# 0001_Page_1.net
KiCad netlist of a schematic drawn in Altium Designer
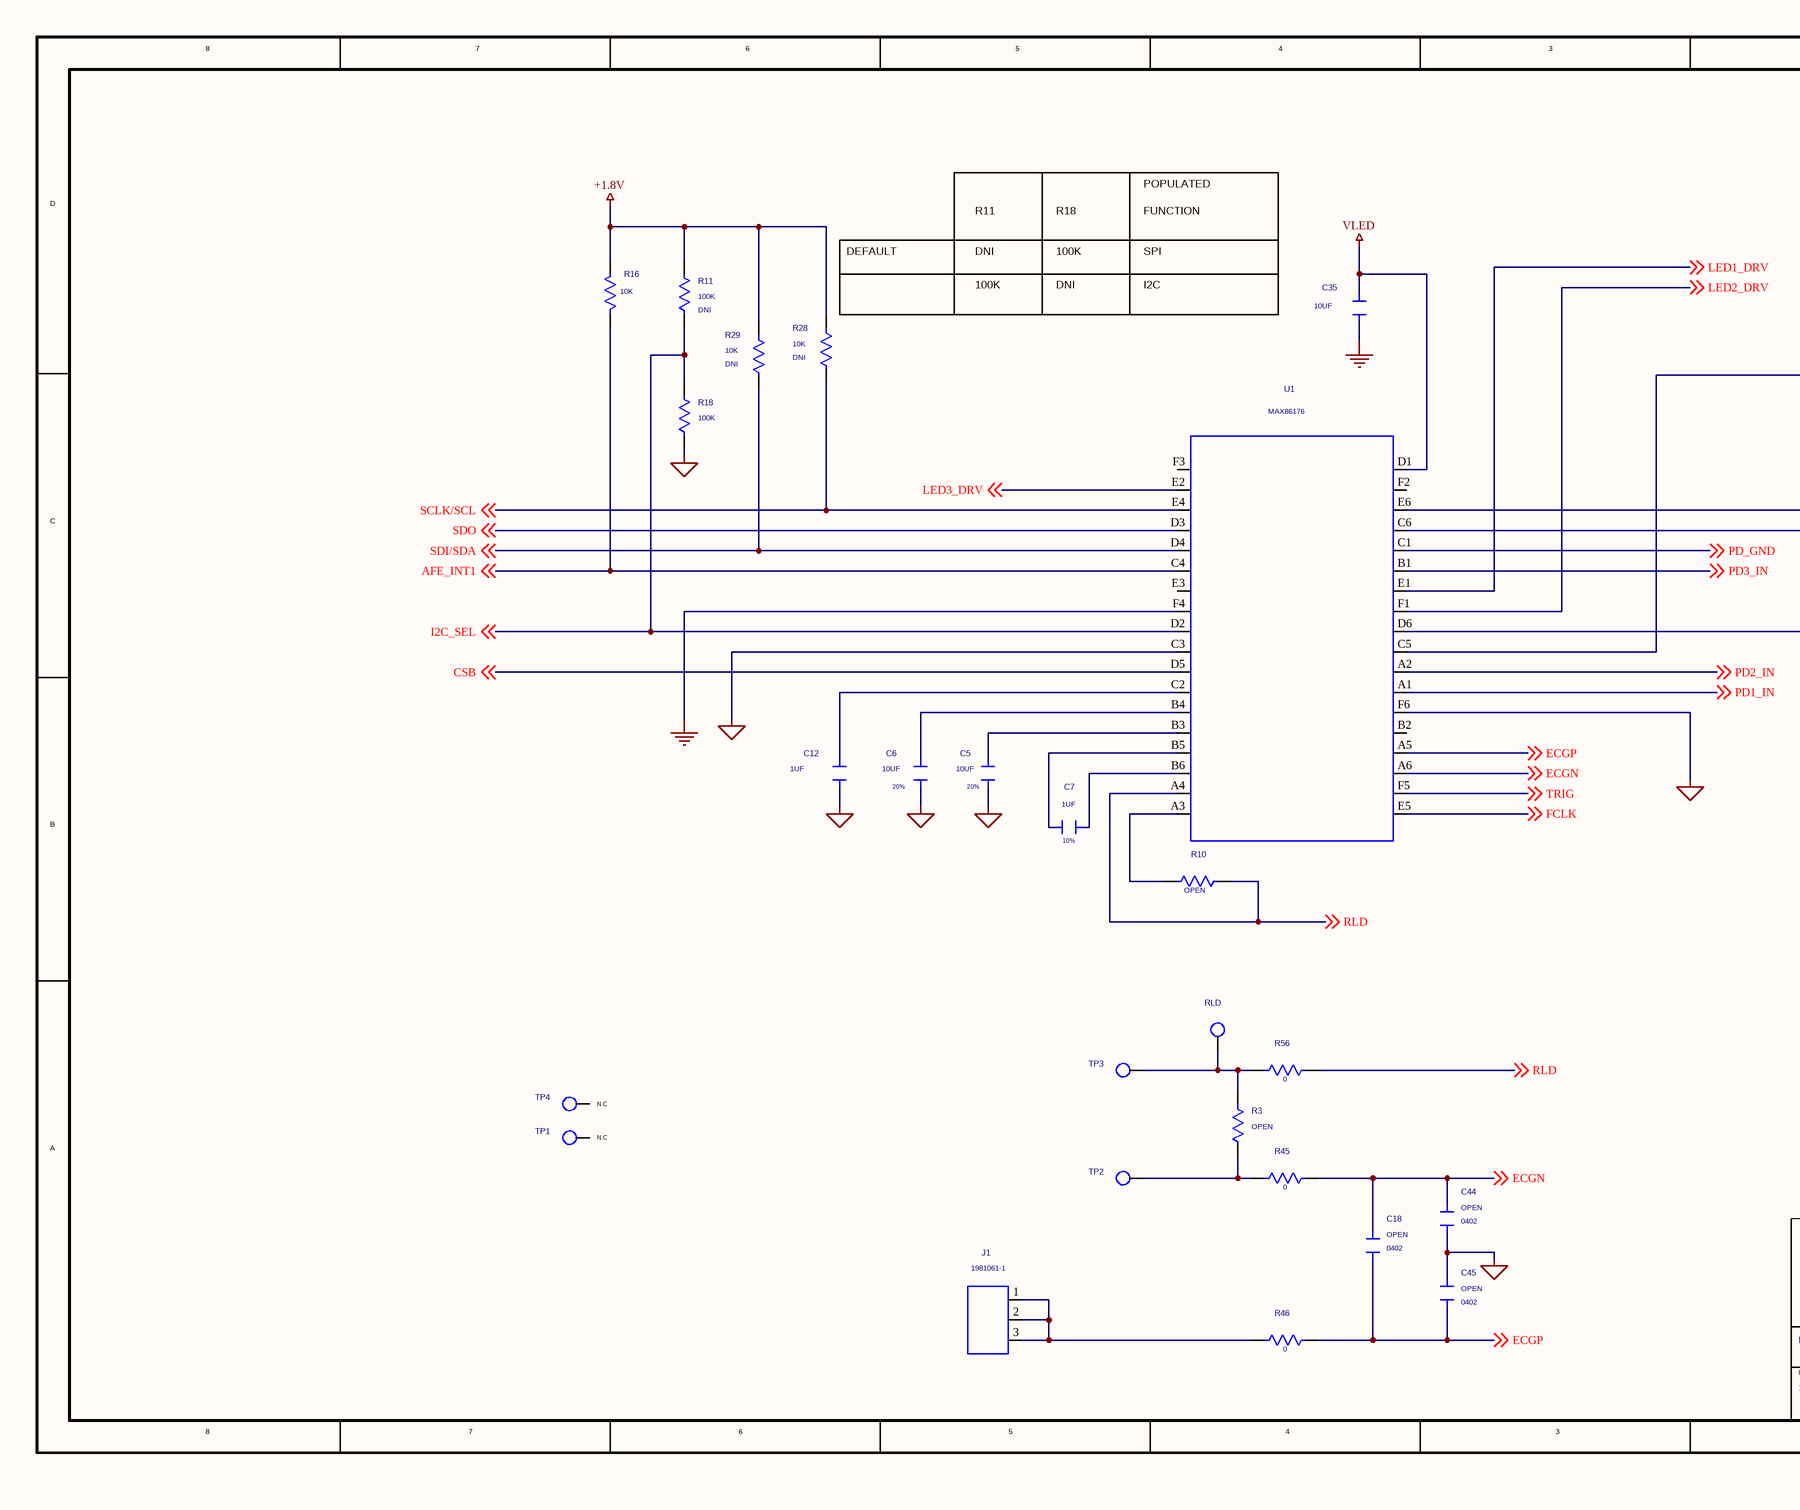
[diagram p0: 0001_Page 1.SchDoc, left]
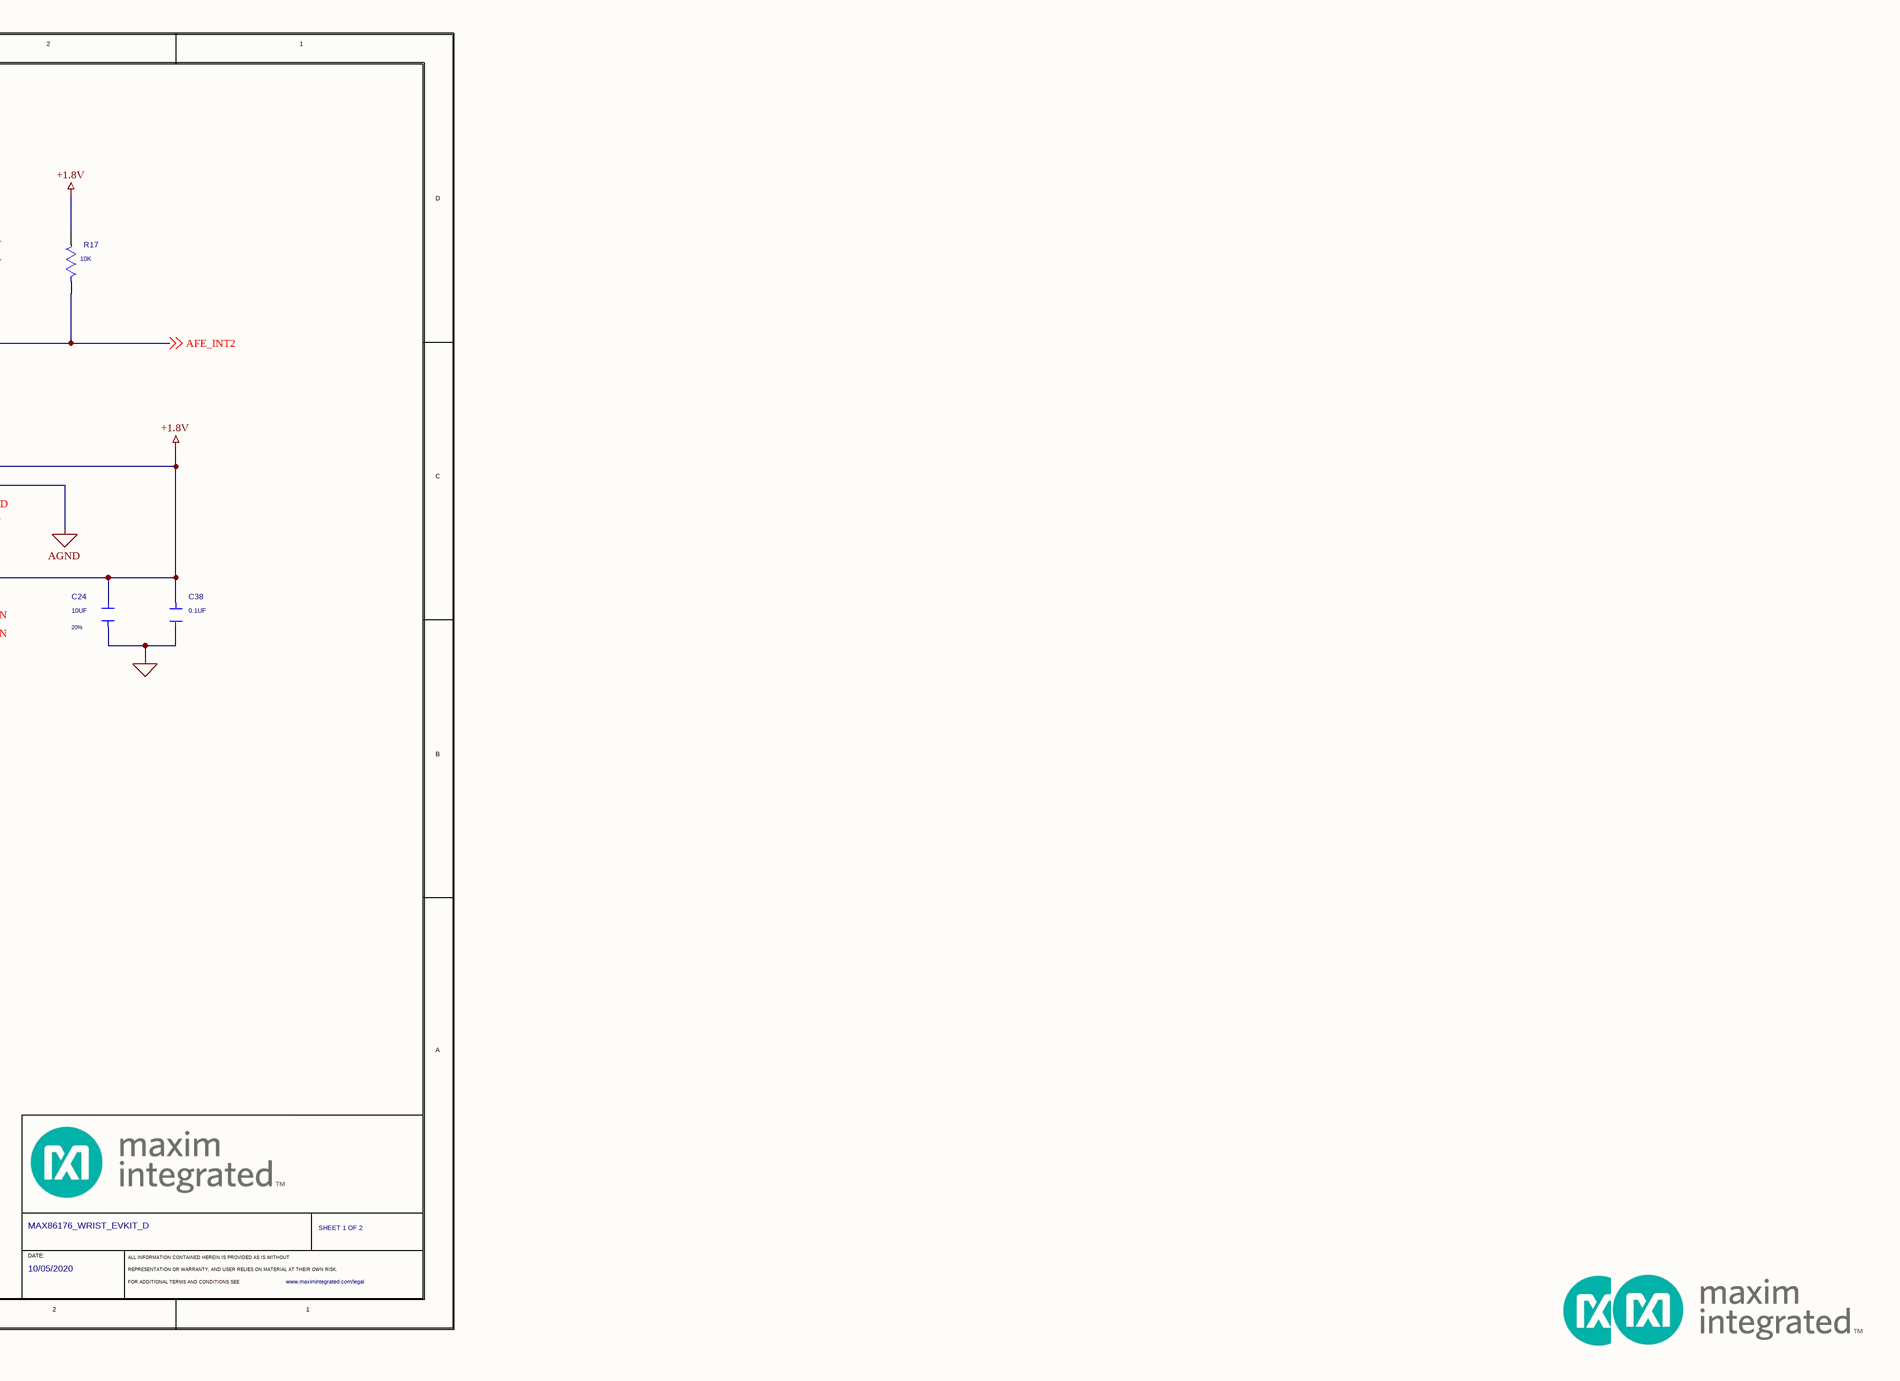
[diagram p1: 0001_Page 1.SchDoc, right]

(export (version "E")
  (design (tool "Eeschema 10.0.6"))
  (components
    (comp (ref "C5")
      (value "10UF")
      (footprint "0402")
      (description "CAP; SMT (0402); 10UF; 20%; 10V; X5R; CERAMIC")
      (fields
        (field (name "MFG_PART_NUMBER") "GRM155R61A106ME44;GRM155R61A106ME11;0402ZD106MAT2A;CL05A106MP5NUNC")
        (field (name "TOLERANCE") "20%")
        (field (name "MANUFACTURER") "MURATA;MURATA;AVX;SAMSUNG")
      )
      (libsource (lib "*") (part "CAP_NP#1"))
    )
    (comp (ref "C6")
      (value "10UF")
      (footprint "0402")
      (description "CAP; SMT (0402); 10UF; 20%; 10V; X5R; CERAMIC")
      (fields
        (field (name "MFG_PART_NUMBER") "GRM155R61A106ME44;GRM155R61A106ME11;0402ZD106MAT2A;CL05A106MP5NUNC")
        (field (name "TOLERANCE") "20%")
        (field (name "MANUFACTURER") "MURATA;MURATA;AVX;SAMSUNG")
      )
      (libsource (lib "*") (part "CAP_NP#1"))
    )
    (comp (ref "C7")
      (value "1UF")
      (footprint "0603")
      (description "CAP; SMT (0603); 1UF; 10%; 25V; X7R; CERAMIC")
      (fields
        (field (name "TOLERANCE") "10%")
        (field (name "MANUFACTURER") "MURATA;TAIYO YUDEN;AVX;TAIYO YUDEN")
      )
      (libsource (lib "*") (part "CAP_NP#1"))
    )
    (comp (ref "C12")
      (value "1UF")
      (footprint "0402")
      (description "CAP; SMT (0402); 1UF; 10%; 16V; X5R; CERAMIC")
      (fields (field (name "MFG_PART_NUMBER") "CL05A105KO5NNN") (field (name "TOLERANCE") "10%"))
      (libsource (lib "*") (part "CAP_NP"))
    )
    (comp (ref "C18")
      (value "OPEN")
      (footprint "0402")
      (description "PACKAGE OUTLINE 0402 NON-POLAR CAPACITOR - EVKIT")
      (fields (field (name "PCB FOOTPRINT_CDS") "0402"))
      (libsource (lib "*") (part "EVK_GENERIC_CAPACITORS"))
    )
    (comp (ref "C24")
      (value "10UF")
      (footprint "0603")
      (description "CAP; SMT (0603); 10UF; 20%; 25V; X5R; CERAMIC CHIP")
      (fields
        (field (name "MFG_PART_NUMBER") "GRM188R61E106MA73")
        (field (name "TOLERANCE") "20%")
        (field (name "MANUFACTURER") "MURATA")
      )
      (libsource (lib "*") (part "EK_CAP_NP#1"))
    )
    (comp (ref "C35")
      (value "10UF")
      (footprint "0603")
      (description "CAP; SMT (0603); 10UF; 20%; 25V; X5R; CERAMIC CHIP")
      (fields (field (name "MFG_PART_NUMBER") "GRM188R61E106MA73") (field (name "TOLERANCE") "20%"))
      (libsource (lib "*") (part "EK_CAP_NP"))
    )
    (comp (ref "C38")
      (value "0.1UF")
      (footprint "0603")
      (description "CAP; SMT (0603); 0.1UF; 10%; 100V; X7R; CERAMIC")
      (fields
        (field (name "MFG_PART_NUMBER") "GRM188R72A104KA35; CC0603KRX7R0BB104")
        (field (name "TOLERANCE") "10%")
      )
      (libsource (lib "*") (part "CAP_NP"))
    )
    (comp (ref "C44")
      (value "OPEN")
      (footprint "0402")
      (description "PACKAGE OUTLINE 0402 NON-POLAR CAPACITOR - EVKIT")
      (fields (field (name "PCB FOOTPRINT_CDS") "0402"))
      (libsource (lib "*") (part "EVK_GENERIC_CAPACITORS"))
    )
    (comp (ref "C45")
      (value "OPEN")
      (footprint "0402")
      (description "PACKAGE OUTLINE 0402 NON-POLAR CAPACITOR - EVKIT")
      (fields (field (name "PCB FOOTPRINT_CDS") "0402"))
      (libsource (lib "*") (part "EVK_GENERIC_CAPACITORS"))
    )
    (comp (ref "J1")
      (value "1981061-1")
      (footprint "TECO_1981061-1")
      (description "CONNECTOR; MALE; SMD; LEAF TYPE BATTERY CONNECTOR; WITHOUT BOSS; 3 PINS")
      (fields (field (name "MANUFACTURER") "TYCO"))
      (libsource (lib "*") (part "1981061-1"))
    )
    (comp (ref "R3")
      (value "OPEN")
      (footprint "RESC0603X33M")
      (description "PACKAGE OUTLINE 0201 RESISTOR - EVKIT")
      (libsource (lib "*") (part "EVK_GENERIC_RESISTORS#1"))
    )
    (comp (ref "R10")
      (value "OPEN")
      (footprint "0402")
      (description "PACKAGE OUTLINE 0402 RESISTOR - EVKIT")
      (libsource (lib "*") (part "EVK_GENERIC_RESISTORS"))
    )
    (comp (ref "R11")
      (value "100K")
      (footprint "0402")
      (description "RES; SMT (0402); 100K; 1%; +/-100PPM/DEGC; 0.1000W")
      (fields
        (field (name "MFG_PART_NUMBER") "ERJ-2RKF1003")
        (field (name "TOLERANCE") "1%")
        (field (name "VARIANT") "DNI")
      )
      (libsource (lib "*") (part "RES_SMD#1"))
    )
    (comp (ref "R16")
      (value "10K")
      (footprint "0402")
      (description "RES; SMT (0402); 10K; 1%; +/-100PPM/DEGC; 0.1000W")
      (fields (field (name "MFG_PART_NUMBER") "ERJ-2RKF1002") (field (name "TOLERANCE") "1%"))
      (libsource (lib "*") (part "RES_SMD"))
    )
    (comp (ref "R17")
      (value "10K")
      (footprint "0402")
      (description "RES; SMT (0402); 10K; 1%; +/-100PPM/DEGC; 0.1000W")
      (fields (field (name "MFG_PART_NUMBER") "ERJ-2RKF1002") (field (name "TOLERANCE") "1%"))
      (libsource (lib "*") (part "RES_SMD"))
    )
    (comp (ref "R18")
      (value "100K")
      (footprint "0402")
      (description "RES; SMT (0402); 100K; 1%; +/-100PPM/DEGC; 0.1000W")
      (fields (field (name "MFG_PART_NUMBER") "ERJ-2RKF1003") (field (name "TOLERANCE") "1%"))
      (libsource (lib "*") (part "RES_SMD#1"))
    )
    (comp (ref "R28")
      (value "10K")
      (footprint "0402")
      (description "RES; SMT (0402); 10K; 1%; +/-100PPM/DEGC; 0.1000W")
      (fields
        (field (name "MFG_PART_NUMBER") "ERJ-2RKF1002")
        (field (name "TOLERANCE") "1%")
        (field (name "VARIANT") "DNI")
      )
      (libsource (lib "*") (part "RES_SMD"))
    )
    (comp (ref "R29")
      (value "10K")
      (footprint "0402")
      (description "RES; SMT (0402); 10K; 1%; +/-100PPM/DEGC; 0.1000W")
      (fields
        (field (name "MFG_PART_NUMBER") "ERJ-2RKF1002")
        (field (name "TOLERANCE") "1%")
        (field (name "VARIANT") "DNI")
      )
      (libsource (lib "*") (part "RES_SMD"))
    )
    (comp (ref "R45")
      (value "0")
      (footprint "0402")
      (description "RES; SMT (0402); 0; JUMPER; JUMPER; 0.1000W")
      (fields (field (name "MFG_PART_NUMBER") "ERJ-2GE0R00") (field (name "TOLERANCE") "0%"))
      (libsource (lib "*") (part "RES_SMD#1"))
    )
    (comp (ref "R46")
      (value "0")
      (footprint "0402")
      (description "RES; SMT (0402); 0; JUMPER; JUMPER; 0.1000W")
      (fields (field (name "MFG_PART_NUMBER") "ERJ-2GE0R00") (field (name "TOLERANCE") "0%"))
      (libsource (lib "*") (part "RES_SMD#1"))
    )
    (comp (ref "R56")
      (value "0")
      (footprint "0402")
      (description "RES; SMT (0402); 0; JUMPER; JUMPER; 0.1000W")
      (fields (field (name "MFG_PART_NUMBER") "ERJ-2GE0R00") (field (name "TOLERANCE") "0%"))
      (libsource (lib "*") (part "RES_SMD#1"))
    )
    (comp (ref "RLD")
      (value "N/A")
      (footprint "TP_C25H12")
      (description "TESTPOINT WITH 12 MILS HOLE DIA, and 25 MILS PAD DIA; NOT FOR COLD TEST")
      (libsource (lib "*") (part "TP"))
    )
    (comp (ref "TP1")
      (value "N/A")
      (footprint "TP_S_SQUARE_3-50")
      (description "TESTPOINT WITH 3.50MM SQUARE PAD DIAMETER")
      (libsource (lib "*") (part "TP"))
    )
    (comp (ref "TP2")
      (value "N/A")
      (footprint "TP_S_SQUARE_3-50")
      (description "TESTPOINT WITH 3.50MM SQUARE PAD DIAMETER")
      (libsource (lib "*") (part "TP"))
    )
    (comp (ref "TP3")
      (value "N/A")
      (footprint "TP_S_SQUARE_3-50")
      (description "TESTPOINT WITH 3.50MM SQUARE PAD DIAMETER")
      (libsource (lib "*") (part "TP"))
    )
    (comp (ref "TP4")
      (value "N/A")
      (footprint "TP_S_SQUARE_3-50")
      (description "TESTPOINT WITH 3.50MM SQUARE PAD DIAMETER")
      (libsource (lib "*") (part "TP"))
    )
    (comp (ref "U1")
      (value "MAX86176")
      (footprint "MAXIM_21-100413")
      (fields (field (name "MANUFACTURER") "MAXIM"))
      (libsource (lib "*") (part "EK_MAX86176"))
    )
  )
  (nets
    (net (code "1") (name "+1.8V") (class "Default")
      (node (ref "C24") (pin "2") (pinfunction "2_2") (pintype "bidirectional"))
      (node (ref "C38") (pin "2") (pinfunction "2_2") (pintype "bidirectional"))
      (node (ref "R11") (pin "2") (pinfunction "2_2") (pintype "bidirectional"))
      (node (ref "R16") (pin "2") (pinfunction "2_2") (pintype "bidirectional"))
      (node (ref "R17") (pin "2") (pinfunction "2_2") (pintype "bidirectional"))
      (node (ref "R28") (pin "1") (pinfunction "1_1") (pintype "bidirectional"))
      (node (ref "R29") (pin "1") (pinfunction "1_1") (pintype "bidirectional"))
      (node (ref "U1") (pin "D6") (pinfunction "D6_D6") (pintype "bidirectional"))
      (node (ref "U1") (pin "E6") (pinfunction "E6_E6") (pintype "bidirectional"))
    )
    (net (code "2") (name "AFE_INT1") (class "Default")
      (node (ref "R16") (pin "1") (pinfunction "1_1") (pintype "bidirectional"))
      (node (ref "U1") (pin "C4") (pinfunction "C4_C4") (pintype "bidirectional"))
    )
    (net (code "3") (name "AFE_INT2") (class "Default")
      (node (ref "R17") (pin "1") (pinfunction "1_1") (pintype "bidirectional"))
      (node (ref "U1") (pin "C5") (pinfunction "C5_C5") (pintype "bidirectional"))
    )
    (net (code "4") (name "AGND") (class "Default")
      (node (ref "C12") (pin "1") (pinfunction "1_1") (pintype "bidirectional"))
      (node (ref "C24") (pin "1") (pinfunction "1_1") (pintype "bidirectional"))
      (node (ref "C38") (pin "1") (pinfunction "1_1") (pintype "bidirectional"))
      (node (ref "C44") (pin "1") (pinfunction "1_1") (pintype "bidirectional"))
      (node (ref "C45") (pin "2") (pinfunction "2_2") (pintype "bidirectional"))
      (node (ref "C5") (pin "1") (pinfunction "1_1") (pintype "bidirectional"))
      (node (ref "C6") (pin "1") (pinfunction "1_1") (pintype "bidirectional"))
      (node (ref "R18") (pin "1") (pinfunction "1_1") (pintype "bidirectional"))
      (node (ref "U1") (pin "C3") (pinfunction "C3_C3") (pintype "bidirectional"))
      (node (ref "U1") (pin "C6") (pinfunction "C6_C6") (pintype "bidirectional"))
      (node (ref "U1") (pin "F6") (pinfunction "F6_F6") (pintype "bidirectional"))
    )
    (net (code "5") (name "CSB") (class "Default")
      (node (ref "U1") (pin "D5") (pinfunction "D5_D5") (pintype "bidirectional"))
    )
    (net (code "6") (name "ECGN") (class "Default")
      (node (ref "C18") (pin "2") (pinfunction "2_2") (pintype "bidirectional"))
      (node (ref "C44") (pin "2") (pinfunction "2_2") (pintype "bidirectional"))
      (node (ref "R45") (pin "2") (pinfunction "2_2") (pintype "bidirectional"))
      (node (ref "U1") (pin "A6") (pinfunction "A6_A6") (pintype "bidirectional"))
    )
    (net (code "7") (name "ECGP") (class "Default")
      (node (ref "C18") (pin "1") (pinfunction "1_1") (pintype "bidirectional"))
      (node (ref "C45") (pin "1") (pinfunction "1_1") (pintype "bidirectional"))
      (node (ref "R46") (pin "2") (pinfunction "2_2") (pintype "bidirectional"))
      (node (ref "U1") (pin "A5") (pinfunction "A5_A5") (pintype "bidirectional"))
    )
    (net (code "8") (name "FCLK") (class "Default")
      (node (ref "U1") (pin "E5") (pinfunction "E5_E5") (pintype "bidirectional"))
    )
    (net (code "9") (name "I2C_SEL") (class "Default")
      (node (ref "R11") (pin "1") (pinfunction "1_1") (pintype "bidirectional"))
      (node (ref "R18") (pin "2") (pinfunction "2_2") (pintype "bidirectional"))
      (node (ref "U1") (pin "D2") (pinfunction "D2_D2") (pintype "bidirectional"))
    )
    (net (code "10") (name "LED1_DRV") (class "Default")
      (node (ref "U1") (pin "E1") (pinfunction "E1_E1") (pintype "bidirectional"))
    )
    (net (code "11") (name "LED2_DRV") (class "Default")
      (node (ref "U1") (pin "F1") (pinfunction "F1_F1") (pintype "bidirectional"))
    )
    (net (code "12") (name "LED3_DRV") (class "Default")
      (node (ref "U1") (pin "E2") (pinfunction "E2_E2") (pintype "bidirectional"))
    )
    (net (code "13") (name "Net-(C5-Pad2)") (class "Default")
      (node (ref "C5") (pin "2") (pinfunction "2_2") (pintype "bidirectional"))
      (node (ref "U1") (pin "B3") (pinfunction "B3_B3") (pintype "bidirectional"))
    )
    (net (code "14") (name "Net-(C6-Pad2)") (class "Default")
      (node (ref "C6") (pin "2") (pinfunction "2_2") (pintype "bidirectional"))
      (node (ref "U1") (pin "B4") (pinfunction "B4_B4") (pintype "bidirectional"))
    )
    (net (code "15") (name "Net-(C7-Pad1)") (class "Default")
      (node (ref "C7") (pin "1") (pinfunction "1_1") (pintype "bidirectional"))
      (node (ref "U1") (pin "B6") (pinfunction "B6_B6") (pintype "bidirectional"))
    )
    (net (code "16") (name "Net-(C7-Pad2)") (class "Default")
      (node (ref "C7") (pin "2") (pinfunction "2_2") (pintype "bidirectional"))
      (node (ref "U1") (pin "B5") (pinfunction "B5_B5") (pintype "bidirectional"))
    )
    (net (code "17") (name "Net-(C12-Pad2)") (class "Default")
      (node (ref "C12") (pin "2") (pinfunction "2_2") (pintype "bidirectional"))
      (node (ref "U1") (pin "C2") (pinfunction "C2_C2") (pintype "bidirectional"))
    )
    (net (code "18") (name "Net-(J1-Pad1)") (class "Default")
      (node (ref "J1") (pin "1") (pinfunction "1_1") (pintype "bidirectional"))
      (node (ref "J1") (pin "2") (pinfunction "2_2") (pintype "bidirectional"))
      (node (ref "J1") (pin "3") (pinfunction "3_3") (pintype "bidirectional"))
      (node (ref "R46") (pin "1") (pinfunction "1_1") (pintype "bidirectional"))
    )
    (net (code "19") (name "Net-(R10-Pad1)") (class "Default")
      (node (ref "R10") (pin "1") (pinfunction "1_1") (pintype "bidirectional"))
      (node (ref "U1") (pin "A3") (pinfunction "A3_A3") (pintype "bidirectional"))
    )
    (net (code "20") (name "Net-(RLD-TP1)") (class "Default")
      (node (ref "R3") (pin "1") (pinfunction "1_1") (pintype "bidirectional"))
      (node (ref "R56") (pin "1") (pinfunction "1_1") (pintype "bidirectional"))
      (node (ref "RLD") (pin "1") (pinfunction "TP1_1") (pintype "bidirectional"))
      (node (ref "TP3") (pin "1") (pinfunction "TP1_1") (pintype "bidirectional"))
    )
    (net (code "21") (name "Net-(TP2-TP1)") (class "Default")
      (node (ref "R3") (pin "2") (pinfunction "2_2") (pintype "bidirectional"))
      (node (ref "R45") (pin "1") (pinfunction "1_1") (pintype "bidirectional"))
      (node (ref "TP2") (pin "1") (pinfunction "TP1_1") (pintype "bidirectional"))
    )
    (net (code "22") (name "PD1_IN") (class "Default")
      (node (ref "U1") (pin "A1") (pinfunction "A1_1_A1") (pintype "bidirectional"))
    )
    (net (code "23") (name "PD2_IN") (class "Default")
      (node (ref "U1") (pin "A2") (pinfunction "A2_A2") (pintype "bidirectional"))
    )
    (net (code "24") (name "PD3_IN") (class "Default")
      (node (ref "U1") (pin "B1") (pinfunction "B1_B1") (pintype "bidirectional"))
    )
    (net (code "25") (name "PD_GND") (class "Default")
      (node (ref "U1") (pin "C1") (pinfunction "C1_C1") (pintype "bidirectional"))
    )
    (net (code "26") (name "PGND") (class "Default")
      (node (ref "C35") (pin "1") (pinfunction "1_1") (pintype "bidirectional"))
      (node (ref "U1") (pin "F4") (pinfunction "F4_F4") (pintype "bidirectional"))
    )
    (net (code "27") (name "RLD") (class "Default")
      (node (ref "R10") (pin "2") (pinfunction "2_2") (pintype "bidirectional"))
      (node (ref "R56") (pin "2") (pinfunction "2_2") (pintype "bidirectional"))
      (node (ref "U1") (pin "A4") (pinfunction "A4_A4") (pintype "bidirectional"))
    )
    (net (code "28") (name "SCLK{slash}SCL") (class "Default")
      (node (ref "R28") (pin "2") (pinfunction "2_2") (pintype "bidirectional"))
      (node (ref "U1") (pin "E4") (pinfunction "E4_E4") (pintype "bidirectional"))
    )
    (net (code "29") (name "SDI{slash}SDA") (class "Default")
      (node (ref "R29") (pin "2") (pinfunction "2_2") (pintype "bidirectional"))
      (node (ref "U1") (pin "D4") (pinfunction "D4_D4") (pintype "bidirectional"))
    )
    (net (code "30") (name "SDO") (class "Default")
      (node (ref "U1") (pin "D3") (pinfunction "D3_D3") (pintype "bidirectional"))
    )
    (net (code "31") (name "TRIG") (class "Default")
      (node (ref "U1") (pin "F5") (pinfunction "F5_F5") (pintype "bidirectional"))
    )
    (net (code "32") (name "VLED") (class "Default")
      (node (ref "C35") (pin "2") (pinfunction "2_2") (pintype "bidirectional"))
      (node (ref "U1") (pin "D1") (pinfunction "D1_D1") (pintype "bidirectional"))
    )
    (net (code "33") (name "unconnected-(TP1-TP1-Pad1)") (class "Default")
      (node (ref "TP1") (pin "1") (pinfunction "TP1_1") (pintype "bidirectional"))
    )
    (net (code "34") (name "unconnected-(TP4-TP1-Pad1)") (class "Default")
      (node (ref "TP4") (pin "1") (pinfunction "TP1_1") (pintype "bidirectional"))
    )
    (net (code "35") (name "unconnected-(U1-PadB2)") (class "Default")
      (node (ref "U1") (pin "B2") (pinfunction "B2_B2") (pintype "bidirectional"))
    )
    (net (code "36") (name "unconnected-(U1-PadE3)") (class "Default")
      (node (ref "U1") (pin "E3") (pinfunction "E3_E3") (pintype "bidirectional"))
    )
    (net (code "37") (name "unconnected-(U1-PadF2)") (class "Default")
      (node (ref "U1") (pin "F2") (pinfunction "F2_F2") (pintype "bidirectional"))
    )
    (net (code "38") (name "unconnected-(U1-PadF3)") (class "Default")
      (node (ref "U1") (pin "F3") (pinfunction "F3_F3") (pintype "bidirectional"))
    )
  )
)
